# LVDS_Channel.net
KiCad netlist of a schematic drawn in Altium Designer
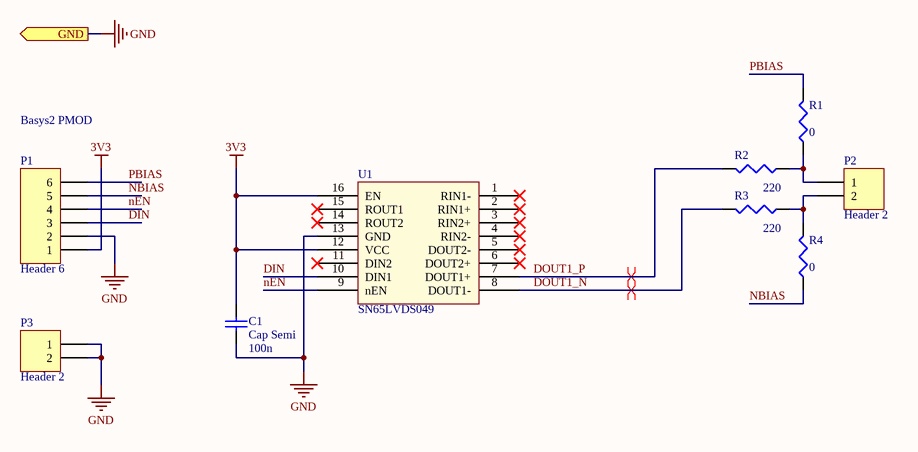
[diagram p0: LVDS_Channel.SchDoc]

(export (version "E")
  (design (tool "Eeschema 10.0.6"))
  (components
    (comp (ref "C1")
      (value "Cap Semi")
      (footprint "1608[0603]")
      (description "Capacitor (Semiconductor SIM Model)")
      (fields (field (name "ALTIUM_VALUE") "100n") (field (name "PUBLISHER") "Altium Limited"))
      (libsource (lib "Miscellaneous Devices") (part "Cap Semi"))
    )
    (comp (ref "P1")
      (value "Header 6")
      (footprint "HDR1X6")
      (description "Header, 6-Pin")
      (fields (field (name "PUBLISHER") "Altium Limited"))
      (libsource (lib "Miscellaneous Connectors") (part "Header 6"))
    )
    (comp (ref "P2")
      (value "Header 2")
      (footprint "HDR1X2")
      (description "Header, 2-Pin")
      (fields (field (name "PUBLISHER") "Altium Limited"))
      (libsource (lib "Miscellaneous Connectors") (part "Header 2"))
    )
    (comp (ref "P3")
      (value "Header 2")
      (footprint "HDR1X2")
      (description "Header, 2-Pin")
      (fields (field (name "PUBLISHER") "Altium Limited"))
      (libsource (lib "") (part "Header 2_1"))
    )
    (comp (ref "R1")
      (value "0")
      (footprint "J1-0603")
      (description "Resistor")
      (fields (field (name "Comment") "Res3") (field (name "PUBLISHER") "Altium Limited"))
      (libsource (lib "Miscellaneous Devices") (part "Res3"))
    )
    (comp (ref "R2")
      (value "220")
      (footprint "J1-0603")
      (description "Resistor")
      (fields (field (name "Comment") "Res3") (field (name "PUBLISHER") "Altium Limited"))
      (libsource (lib "Miscellaneous Devices") (part "Res3"))
    )
    (comp (ref "R3")
      (value "220")
      (footprint "J1-0603")
      (description "Resistor")
      (fields (field (name "Comment") "Res3") (field (name "PUBLISHER") "Altium Limited"))
      (libsource (lib "Miscellaneous Devices") (part "Res3"))
    )
    (comp (ref "R4")
      (value "0")
      (footprint "J1-0603")
      (description "Resistor")
      (fields (field (name "Comment") "Res3") (field (name "PUBLISHER") "Altium Limited"))
      (libsource (lib "Miscellaneous Devices") (part "Res3"))
    )
    (comp (ref "U1")
      (value "SN65LVDS049")
      (footprint "SOP127P600-8N")
      (libsource (lib "Schlib1") (part "SN65LVDS049"))
    )
  )
  (nets
    (net (code "1") (name "/DIN") (class "Default")
      (node (ref "P1") (pin "3") (pinfunction "3_3") (pintype "passive"))
      (node (ref "U1") (pin "10") (pinfunction "DIN1_10") (pintype "passive"))
    )
    (net (code "2") (name "/DOUT1_N") (class "Default")
      (node (ref "R3") (pin "2") (pinfunction "2_2") (pintype "passive"))
      (node (ref "U1") (pin "8") (pinfunction "DOUT1-_8") (pintype "passive"))
    )
    (net (code "3") (name "/DOUT1_P") (class "Default")
      (node (ref "R2") (pin "2") (pinfunction "2_2") (pintype "passive"))
      (node (ref "U1") (pin "7") (pinfunction "DOUT1+_7") (pintype "passive"))
    )
    (net (code "4") (name "/NBIAS") (class "Default")
      (node (ref "P1") (pin "5") (pinfunction "5_5") (pintype "passive"))
      (node (ref "R4") (pin "1") (pinfunction "1_1") (pintype "passive"))
    )
    (net (code "5") (name "/PBIAS") (class "Default")
      (node (ref "P1") (pin "6") (pinfunction "6_6") (pintype "passive"))
      (node (ref "R1") (pin "2") (pinfunction "2_2") (pintype "passive"))
    )
    (net (code "6") (name "/nEN") (class "Default")
      (node (ref "P1") (pin "4") (pinfunction "4_4") (pintype "passive"))
      (node (ref "U1") (pin "9") (pinfunction "nEN_9") (pintype "passive"))
    )
    (net (code "7") (name "3V3") (class "Default")
      (node (ref "C1") (pin "2") (pinfunction "2_2") (pintype "passive"))
      (node (ref "P1") (pin "1") (pinfunction "1_1") (pintype "passive"))
      (node (ref "U1") (pin "12") (pinfunction "VCC_12") (pintype "passive"))
      (node (ref "U1") (pin "16") (pinfunction "EN_16") (pintype "passive"))
    )
    (net (code "8") (name "GND") (class "Default")
      (node (ref "C1") (pin "1") (pinfunction "1_1") (pintype "passive"))
      (node (ref "P1") (pin "2") (pinfunction "2_2") (pintype "passive"))
      (node (ref "P3") (pin "1") (pinfunction "1_1") (pintype "passive"))
      (node (ref "P3") (pin "2") (pinfunction "2_2") (pintype "passive"))
      (node (ref "U1") (pin "13") (pinfunction "GND_13") (pintype "passive"))
    )
    (net (code "9") (name "Net-(P2-Pad1)") (class "Default")
      (node (ref "P2") (pin "1") (pinfunction "1_1") (pintype "passive"))
      (node (ref "R1") (pin "1") (pinfunction "1_1") (pintype "passive"))
      (node (ref "R2") (pin "1") (pinfunction "1_1") (pintype "passive"))
    )
    (net (code "10") (name "Net-(P2-Pad2)") (class "Default")
      (node (ref "P2") (pin "2") (pinfunction "2_2") (pintype "passive"))
      (node (ref "R3") (pin "1") (pinfunction "1_1") (pintype "passive"))
      (node (ref "R4") (pin "2") (pinfunction "2_2") (pintype "passive"))
    )
    (net (code "11") (name "unconnected-(U1-DIN2-Pad11)") (class "Default")
      (node (ref "U1") (pin "11") (pinfunction "DIN2_11") (pintype "passive+no_connect"))
    )
    (net (code "12") (name "unconnected-(U1-DOUT2+-Pad6)") (class "Default")
      (node (ref "U1") (pin "6") (pinfunction "DOUT2+_6") (pintype "passive+no_connect"))
    )
    (net (code "13") (name "unconnected-(U1-DOUT2--Pad5)") (class "Default")
      (node (ref "U1") (pin "5") (pinfunction "DOUT2-_5") (pintype "passive+no_connect"))
    )
    (net (code "14") (name "unconnected-(U1-RIN1+-Pad2)") (class "Default")
      (node (ref "U1") (pin "2") (pinfunction "RIN1+_2") (pintype "passive+no_connect"))
    )
    (net (code "15") (name "unconnected-(U1-RIN1--Pad1)") (class "Default")
      (node (ref "U1") (pin "1") (pinfunction "RIN1-_1") (pintype "passive+no_connect"))
    )
    (net (code "16") (name "unconnected-(U1-RIN2+-Pad3)") (class "Default")
      (node (ref "U1") (pin "3") (pinfunction "RIN2+_3") (pintype "passive+no_connect"))
    )
    (net (code "17") (name "unconnected-(U1-RIN2--Pad4)") (class "Default")
      (node (ref "U1") (pin "4") (pinfunction "RIN2-_4") (pintype "passive+no_connect"))
    )
    (net (code "18") (name "unconnected-(U1-ROUT1-Pad15)") (class "Default")
      (node (ref "U1") (pin "15") (pinfunction "ROUT1_15") (pintype "passive+no_connect"))
    )
    (net (code "19") (name "unconnected-(U1-ROUT2-Pad14)") (class "Default")
      (node (ref "U1") (pin "14") (pinfunction "ROUT2_14") (pintype "passive+no_connect"))
    )
  )
)
